# RP2350B.net
KiCad netlist of a schematic drawn in Altium Designer
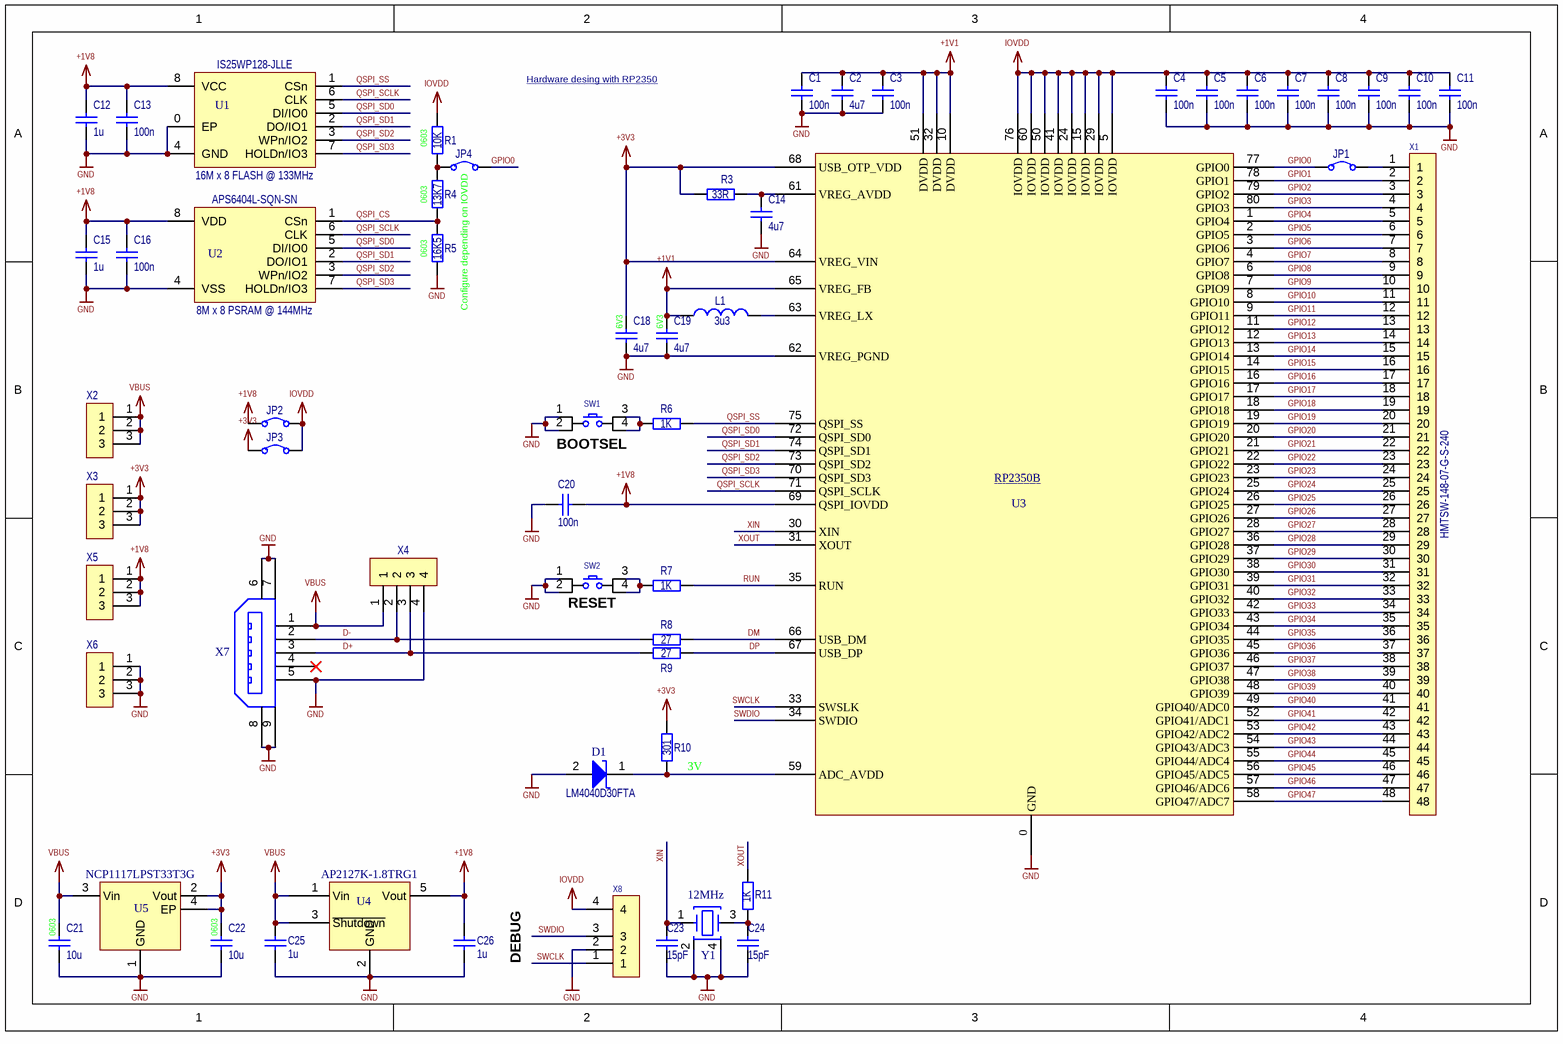
[diagram p0: RP2350B.SchDoc]

(export (version "E")
  (design (tool "Eeschema 10.0.6"))
  (components
    (comp (ref "C1")
      (value "100n")
      (footprint "CAPC0402")
      (description "Capacitor; Ceramic; 100n; 2; 10V; X7R; 5%; -55°C ~ 125°C")
      (fields (field (name "Comment") "C0402C104J8RACTU"))
      (libsource (lib "Capacitors") (part "100n_0402_10V_X7R_5%"))
    )
    (comp (ref "C2")
      (value "4u7")
      (footprint "CAPC0402")
      (description "Capacitor; Ceramic; 4.7u; 0402; 10V; X5R; 10%; -55°C ~ 85°C")
      (fields
        (field (name "MANUFACTURER") "Samsung Electro-Mechanics")
        (field (name "MANUFACTURER PART NUMBER") "CL05A475KP5NRNC")
      )
      (libsource (lib "Capacitors") (part "4u7_0402_10V_X5R_10%"))
    )
    (comp (ref "C3")
      (value "100n")
      (footprint "CAPC0402")
      (description "Capacitor; Ceramic; 100n; 0402; 10V; X7R; 5%; -55°C ~ 125°C")
      (fields (field (name "Comment") "C0402C104J8RACTU"))
      (libsource (lib "Capacitors") (part "100n_0402_10V_X7R_5%"))
    )
    (comp (ref "C4")
      (value "100n")
      (footprint "CAPC0402")
      (description "Capacitor; Ceramic; 100n; 0402; 10V; X7R; 5%; -55°C ~ 125°C")
      (fields (field (name "Comment") "C0402C104J8RACTU"))
      (libsource (lib "Capacitors") (part "100n_0402_10V_X7R_5%"))
    )
    (comp (ref "C5")
      (value "100n")
      (footprint "CAPC0402")
      (description "Capacitor; Ceramic; 100n; 0402; 10V; X7R; 5%; -55°C ~ 125°C")
      (fields (field (name "Comment") "C0402C104J8RACTU"))
      (libsource (lib "Capacitors") (part "100n_0402_10V_X7R_5%"))
    )
    (comp (ref "C6")
      (value "100n")
      (footprint "CAPC0402")
      (description "Capacitor; Ceramic; 100n; 0402; 10V; X7R; 5%; -55°C ~ 125°C")
      (fields (field (name "Comment") "C0402C104J8RACTU"))
      (libsource (lib "Capacitors") (part "100n_0402_10V_X7R_5%"))
    )
    (comp (ref "C7")
      (value "100n")
      (footprint "CAPC0402")
      (description "Capacitor; Ceramic; 100n; 0402; 10V; X7R; 5%; -55°C ~ 125°C")
      (fields (field (name "Comment") "C0402C104J8RACTU"))
      (libsource (lib "Capacitors") (part "100n_0402_10V_X7R_5%"))
    )
    (comp (ref "C8")
      (value "100n")
      (footprint "CAPC0402")
      (description "Capacitor; Ceramic; 100n; 0402; 10V; X7R; 5%; -55°C ~ 125°C")
      (fields (field (name "Comment") "C0402C104J8RACTU"))
      (libsource (lib "Capacitors") (part "100n_0402_10V_X7R_5%"))
    )
    (comp (ref "C9")
      (value "100n")
      (footprint "CAPC0402")
      (description "Capacitor; Ceramic; 100n; 0402; 10V; X7R; 5%; -55°C ~ 125°C")
      (fields (field (name "Comment") "C0402C104J8RACTU"))
      (libsource (lib "Capacitors") (part "100n_0402_10V_X7R_5%"))
    )
    (comp (ref "C10")
      (value "100n")
      (footprint "CAPC0402")
      (description "Capacitor; Ceramic; 100n; 0402; 10V; X7R; 5%; -55°C ~ 125°C")
      (fields (field (name "Comment") "C0402C104J8RACTU"))
      (libsource (lib "Capacitors") (part "100n_0402_10V_X7R_5%"))
    )
    (comp (ref "C11")
      (value "100n")
      (footprint "CAPC0402")
      (description "Capacitor; Ceramic; 100n; 0402; 10V; X7R; 5%; -55°C ~ 125°C")
      (fields (field (name "Comment") "C0402C104J8RACTU"))
      (libsource (lib "Capacitors") (part "100n_0402_10V_X7R_5%"))
    )
    (comp (ref "C12")
      (value "1u")
      (footprint "CAPC0402")
      (description "Capacitor; Ceramic; 1u; 0402; 10V; X5R; 10%; -55°C ~ 85°C")
      (fields
        (field (name "MANUFACTURER") "Samsung Electro-Mechanics")
        (field (name "MANUFACTURER PART NUMBER") "CL05A105KP5NNNC")
      )
      (libsource (lib "Capacitors") (part "1u_0402_10V_X5R_10%"))
    )
    (comp (ref "C13")
      (value "100n")
      (footprint "CAPC0402")
      (description "Capacitor; Ceramic; 100n; 0402; 10V; X7R; 5%; -55°C ~ 125°C")
      (fields (field (name "Comment") "C0402C104J8RACTU"))
      (libsource (lib "Capacitors") (part "100n_0402_10V_X7R_5%"))
    )
    (comp (ref "C14")
      (value "4u7")
      (footprint "CAPC0402")
      (description "Capacitor; Ceramic; 4.7u; 0402; 10V; X5R; 10%; -55°C ~ 85°C")
      (fields
        (field (name "MANUFACTURER") "Samsung Electro-Mechanics")
        (field (name "MANUFACTURER PART NUMBER") "CL05A475KP5NRNC")
      )
      (libsource (lib "Capacitors") (part "4u7_0402_10V_X5R_10%"))
    )
    (comp (ref "C15")
      (value "1u")
      (footprint "CAPC0402")
      (description "Capacitor; Ceramic; 1u; 0402; 10V; X5R; 10%; -55°C ~ 85°C")
      (fields
        (field (name "MANUFACTURER") "Samsung Electro-Mechanics")
        (field (name "MANUFACTURER PART NUMBER") "CL05A105KP5NNNC")
      )
      (libsource (lib "Capacitors") (part "1u_0402_10V_X5R_10%"))
    )
    (comp (ref "C16")
      (value "100n")
      (footprint "CAPC0402")
      (description "Capacitor; Ceramic; 100n; 0402; 10V; X7R; 5%; -55°C ~ 125°C")
      (fields (field (name "Comment") "C0402C104J8RACTU"))
      (libsource (lib "Capacitors") (part "100n_0402_10V_X7R_5%"))
    )
    (comp (ref "C18")
      (value "6V3")
      (footprint "CAPC0603")
      (description "Capacitor; Ceramic; 4.7u; 0603; 6.3V; X7S; 10%; -55°C ~ 125°C")
      (fields
        (field (name "MANUFACTURER") "Murata Electronics")
        (field (name "MANUFACTURER PART NUMBER") "GCJ188C70J475KE02D")
        (field (name "ALTIUM_VALUE") "4u7")
      )
      (libsource (lib "symbols") (part "4u7_0603_6V3_X7S_10%"))
    )
    (comp (ref "C19")
      (value "6V3")
      (footprint "CAPC0603")
      (description "Capacitor; Ceramic; 4.7u; 0603; 6.3V; X7S; 10%; -55°C ~ 125°C")
      (fields
        (field (name "MANUFACTURER") "Murata Electronics")
        (field (name "MANUFACTURER PART NUMBER") "GCJ188C70J475KE02D")
        (field (name "ALTIUM_VALUE") "4u7")
      )
      (libsource (lib "symbols") (part "4u7_0603_6V3_X7S_10%"))
    )
    (comp (ref "C20")
      (value "100n")
      (footprint "CAPC0402")
      (description "Capacitor; Ceramic; 100n; 0402; 10V; X7R; 5%; -55°C ~ 125°C")
      (fields (field (name "Comment") "C0402C104J8RACTU"))
      (libsource (lib "Capacitors") (part "100n_0402_10V_X7R_5%"))
    )
    (comp (ref "C21")
      (value "0603")
      (footprint "CAPC0603")
      (description "Capacitor; Ceramic; 10u; 0603; 16V; X5R; 10%; -55°C ~ 85°C")
      (fields (field (name "ALTIUM_VALUE") "10u"))
      (libsource (lib "Capacitors") (part "10u_0603_16V_X5R_10%"))
    )
    (comp (ref "C22")
      (value "0603")
      (footprint "CAPC0603")
      (description "Capacitor; Ceramic; 10u; 0603; 16V; X5R; 10%; -55°C ~ 85°C")
      (fields (field (name "ALTIUM_VALUE") "10u"))
      (libsource (lib "Capacitors") (part "10u_0603_16V_X5R_10%"))
    )
    (comp (ref "C23")
      (value "15pF")
      (footprint "CAPC0402")
      (description "Capacitor; Ceramic; 15p; 0402; 25V; C0G/NP0; +/-5%; -55°C ~ 125°C")
      (fields
        (field (name "MANUFACTURER") "YAGEO")
        (field (name "MANUFACTURER PART NUMBER") "CC0402JRNPO8BN150")
      )
      (libsource (lib "symbols") (part "15p_0402_25V_C0G/NP0_5%"))
    )
    (comp (ref "C24")
      (value "15pF")
      (footprint "CAPC0402")
      (description "Capacitor; Ceramic; 15p; 0402; 25V; C0G/NP0; +/-5%; -55°C ~ 125°C")
      (fields
        (field (name "MANUFACTURER") "YAGEO")
        (field (name "MANUFACTURER PART NUMBER") "CC0402JRNPO8BN150")
      )
      (libsource (lib "symbols") (part "15p_0402_25V_C0G/NP0_5%"))
    )
    (comp (ref "C25")
      (value "1u")
      (footprint "CAPC0402")
      (description "Capacitor; Ceramic; 1u; 0402; 10V; X5R; 10%; -55°C ~ 85°C")
      (fields
        (field (name "MANUFACTURER") "Samsung Electro-Mechanics")
        (field (name "MANUFACTURER PART NUMBER") "CL05A105KP5NNNC")
      )
      (libsource (lib "Capacitors") (part "1u_0402_10V_X5R_10%"))
    )
    (comp (ref "C26")
      (value "1u")
      (footprint "CAPC0402")
      (description "Capacitor; Ceramic; 1u; 0402; 10V; X5R; 10%; -55°C ~ 85°C")
      (fields
        (field (name "MANUFACTURER") "Samsung Electro-Mechanics")
        (field (name "MANUFACTURER PART NUMBER") "CL05A105KP5NNNC")
      )
      (libsource (lib "Capacitors") (part "1u_0402_10V_X5R_10%"))
    )
    (comp (ref "D1")
      (value "LM4040D30FTA")
      (footprint "SOT23-3")
      (description "Shunt Voltage Reference IC Fixed 3V ±1% 15 mA SOT-23-3")
      (fields (field (name "MANUFACTURER") "Diodes Incorporated") (field (name "ALTIUM_VALUE") "3V"))
      (libsource (lib "symbols") (part "LM4040D30FTA"))
    )
    (comp (ref "JP1")
      (value "5110 Keystone")
      (footprint "JumperSMD_0603")
      (description "Jumper; Chip; 0R; 0603; 500mW")
      (fields (field (name "MANUFACTURER") "Keystone") (field (name "MANUFACTURER PART NUMBER") "5110"))
      (libsource (lib "Jumpers") (part "JMP_0R_0603"))
    )
    (comp (ref "JP2")
      (value "5110 Keystone")
      (footprint "JumperSMD_0603")
      (description "Jumper; Chip; 0R; 0603; 500mW")
      (fields (field (name "MANUFACTURER") "Keystone") (field (name "MANUFACTURER PART NUMBER") "5110"))
      (libsource (lib "Jumpers") (part "JMP_0R_0603"))
    )
    (comp (ref "JP3")
      (value "5110 Keystone")
      (footprint "JumperSMD_0603")
      (description "Jumper; Chip; 0R; 0603; 500mW")
      (fields (field (name "MANUFACTURER") "Keystone") (field (name "MANUFACTURER PART NUMBER") "5110"))
      (libsource (lib "Jumpers") (part "JMP_0R_0603"))
    )
    (comp (ref "JP4")
      (value "5110 Keystone")
      (footprint "JumperSMD_0603")
      (description "Jumper; Chip; 0R; 0603; 500mW")
      (fields (field (name "MANUFACTURER") "Keystone") (field (name "MANUFACTURER PART NUMBER") "5110"))
      (libsource (lib "Jumpers") (part "JMP_0R_0603"))
    )
    (comp (ref "L1")
      (value "3u3")
      (footprint "IND_0806")
      (description "3.3 µH Shielded Inductor 1.4 A 225mOhm Max 0806")
      (fields
        (field (name "MANUFACTURER") "Bourns Inc.")
        (field (name "MANUFACTURER PART NUMBER") "SRP2010DPA-3R3M")
      )
      (libsource (lib "Inductances") (part "IND_3u3_2X1.6mm_1.4A_20%"))
    )
    (comp (ref "R1")
      (value "0603")
      (footprint "RESC0603")
      (description "Resistor; Chip; 10k; 0603; 75V; 1%; 100ppm; 100mW; -55°C ~ 155°C")
      (fields (field (name "ALTIUM_VALUE") "10K"))
      (libsource (lib "Resistors") (part "10K_0603_100mW_1%_100ppm"))
    )
    (comp (ref "R3")
      (value "33R")
      (footprint "RESC0402")
      (description "Resistor; Chip; 33R; 0402; 50V; 1%; 100ppm; 63mW; -55°C ~ 155°C")
      (fields
        (field (name "MANUFACTURER") "Yageo")
        (field (name "MANUFACTURER PART NUMBER") "RC0402FR-0733RL")
      )
      (libsource (lib "Resistors") (part "33R_0402_63mW_1%_100ppm"))
    )
    (comp (ref "R4")
      (value "0603")
      (footprint "RESC0603")
      (description "Resistor; Chip; 13K7; 0603; 0.1%; 25ppm; 100mW; -55°C ~ 155°C")
      (fields
        (field (name "MANUFACTURER") "YAGEO")
        (field (name "MANUFACTURER PART NUMBER") "RT0603BRD0713K7L")
        (field (name "ALTIUM_VALUE") "13K7")
      )
      (libsource (lib "symbols") (part "13K7_0603_100mW_0.1%_25ppm"))
    )
    (comp (ref "R5")
      (value "0603")
      (footprint "RESC0603")
      (description "Resistor; Chip; 16K5; 0603; 0.1%; 25ppm; 100mW; -55°C ~ 155°C")
      (fields
        (field (name "MANUFACTURER") "YAGEO")
        (field (name "MANUFACTURER PART NUMBER") "RT0603BRD0716K5L")
        (field (name "ALTIUM_VALUE") "16K5")
      )
      (libsource (lib "symbols") (part "16K5_0603_100mW_0.1%_25ppm"))
    )
    (comp (ref "R6")
      (value "1K")
      (footprint "RESC0402")
      (description "Resistor; Chip; 1k; 0402; 50V; 1%; 100ppm; 63mW; -55°C ~ 155°C")
      (fields
        (field (name "MANUFACTURER") "Yageo")
        (field (name "MANUFACTURER PART NUMBER") "RC0402FR-071KL")
      )
      (libsource (lib "Resistors") (part "1K_0402_63mW_1%_100ppm"))
    )
    (comp (ref "R7")
      (value "1K")
      (footprint "RESC0402")
      (description "Resistor; Chip; 1k; 0402; 50V; 1%; 100ppm; 63mW; -55°C ~ 155°C")
      (fields
        (field (name "MANUFACTURER") "Yageo")
        (field (name "MANUFACTURER PART NUMBER") "RC0402FR-071KL")
      )
      (libsource (lib "Resistors") (part "1K_0402_63mW_1%_100ppm"))
    )
    (comp (ref "R8")
      (value "27")
      (footprint "RESC0402")
      (description "Resistor; Chip; 27Ohm; 0402; 1%; 100ppm; 63mW; -55°C ~ 155°C")
      (fields
        (field (name "MANUFACTURER") "YAGEO")
        (field (name "MANUFACTURER PART NUMBER") "RC0402FR-0727RL")
      )
      (libsource (lib "symbols") (part "27R_0402_63mW_1%_100ppm"))
    )
    (comp (ref "R9")
      (value "27")
      (footprint "RESC0402")
      (description "Resistor; Chip; 27Ohm; 0402; 1%; 100ppm; 63mW; -55°C ~ 155°C")
      (fields
        (field (name "MANUFACTURER") "YAGEO")
        (field (name "MANUFACTURER PART NUMBER") "RC0402FR-0727RL")
      )
      (libsource (lib "symbols") (part "27R_0402_63mW_1%_100ppm"))
    )
    (comp (ref "R10")
      (value "301")
      (footprint "RESC0402")
      (description "Resistor; Chip; 301R; 0402; 1%; 100ppm; 63mW; -55°C ~ 155°C")
      (fields
        (field (name "MANUFACTURER") "YAGEO")
        (field (name "MANUFACTURER PART NUMBER") "RC0402FR-07301RL")
      )
      (libsource (lib "symbols") (part "301R_0402_63mW_1%_100ppm"))
    )
    (comp (ref "R11")
      (value "1K")
      (footprint "RESC0402")
      (description "Resistor; Chip; 1k; 0402; 50V; 1%; 100ppm; 63mW; -55°C ~ 155°C")
      (fields
        (field (name "MANUFACTURER") "Yageo")
        (field (name "MANUFACTURER PART NUMBER") "RC0402FR-071KL")
      )
      (libsource (lib "") (part "1K_0402_63mW_1%_100ppm_1"))
    )
    (comp (ref "SW1")
      (value "434133025816")
      (footprint "434133025816")
      (description "SWITCH TACTILE SPST-NO 0.05A 16V")
      (fields (field (name "MANUFACTURER") "Würth Elektronik"))
      (libsource (lib "symbols") (part "434133025816"))
    )
    (comp (ref "SW2")
      (value "434133025816")
      (footprint "434133025816")
      (description "SWITCH TACTILE SPST-NO 0.05A 16V")
      (fields (field (name "MANUFACTURER") "Würth Elektronik"))
      (libsource (lib "symbols") (part "434133025816"))
    )
    (comp (ref "U1")
      (value "16M x 8 FLASH @ 133MHz")
      (footprint "WSON8-6x8")
      (description "IC FLASH 128MBIT SPI/QUAD 8WSON")
      (fields
        (field (name "MANUFACTURER") "ISSI, Integrated Silicon Solution Inc")
        (field (name "MANUFACTURER PART NUMBER") "IS25WP128-JLLE")
        (field (name "Comment") "IS25WP128-JLLE")
      )
      (libsource (lib "symbols") (part "IS25WP128-JLLE"))
    )
    (comp (ref "U2")
      (value "8M x 8 PSRAM @ 144MHz")
      (footprint "SOP-8L (150)")
      (description "IC PSRAM 64MBIT QSPI SOP-8L")
      (fields
        (field (name "MANUFACTURER") "AP Memory")
        (field (name "MANUFACTURER PART NUMBER") "APS6404L-SQN-SN")
        (field (name "Comment") "APS6404L-SQN-SN")
      )
      (libsource (lib "symbols") (part "APS6404L-SQN-SN"))
    )
    (comp (ref "U3")
      (value "RP2350B")
      (footprint "QFN-80")
      (description "IC MCU 32BIT EXT MEM 80QFN")
      (libsource (lib "symbols") (part "RP2350B"))
    )
    (comp (ref "U4")
      (value "AP2127K-1.8TRG1")
      (footprint "SOT23-5")
      (description "IC REG LINEAR 1.8V 300MA SOT23-5")
      (fields
        (field (name "MANUFACTURER") "Diodes Incorporated")
        (field (name "MANUFACTURER PART NUMBER") "AP2127K-1.8TRG1")
      )
      (libsource (lib "symbols") (part "AP2127K-1.8TRG1"))
    )
    (comp (ref "U5")
      (value "NCP1117LPST33T3G")
      (footprint "SOT-232-4")
      (description "IC REG LINEAR 3.3V 1A SOT223")
      (fields (field (name "MANUFACTURER") "onsemi"))
      (libsource (lib "symbols") (part "NCP1117LPST33T3G"))
    )
    (comp (ref "X1")
      (value "HMTSW-148-07-G-S-240")
      (footprint "HDR_TH_1X48_M_00")
      (description "Header; 1x48 pins; Male; Straight; Pitch 2.54mm; Samtec HMTSW Series")
      (libsource (lib "symbols") (part "HDR_TH_1X48_M_00"))
    )
    (comp (ref "X2")
      (value "825433-3")
      (footprint "HDR_TH_1X3_M_00")
      (description "Header; 1x3 pins; Male; Straight; Pitch 2.54mm")
      (fields
        (field (name "MANUFACTURER") "TE Connectivity")
        (field (name "MANUFACTURER PART NUMBER") "825433-2")
      )
      (libsource (lib "Connections") (part "HDR_TH_1X3_M_00"))
    )
    (comp (ref "X3")
      (value "825433-3")
      (footprint "HDR_TH_1X3_M_00")
      (description "Header; 1x3 pins; Male; Straight; Pitch 2.54mm")
      (fields
        (field (name "MANUFACTURER") "TE Connectivity")
        (field (name "MANUFACTURER PART NUMBER") "825433-2")
      )
      (libsource (lib "Connections") (part "HDR_TH_1X3_M_00"))
    )
    (comp (ref "X4")
      (value "HMTSW-104-07-G-S-240")
      (footprint "HDR_TH_1X4_M_00")
      (description "Header; 1x4 pins; Male; Straight; Pitch 2.54mm; Samtec HMTSW Series")
      (libsource (lib "symbols") (part "HDR_TH_1X4_M_00"))
    )
    (comp (ref "X5")
      (value "825433-3")
      (footprint "HDR_TH_1X3_M_00")
      (description "Header; 1x3 pins; Male; Straight; Pitch 2.54mm")
      (fields
        (field (name "MANUFACTURER") "TE Connectivity")
        (field (name "MANUFACTURER PART NUMBER") "825433-2")
      )
      (libsource (lib "Connections") (part "HDR_TH_1X3_M_00"))
    )
    (comp (ref "X6")
      (value "825433-3")
      (footprint "HDR_TH_1X3_M_00")
      (description "Header; 1x3 pins; Male; Straight; Pitch 2.54mm")
      (fields
        (field (name "MANUFACTURER") "TE Connectivity")
        (field (name "MANUFACTURER PART NUMBER") "825433-2")
      )
      (libsource (lib "Connections") (part "HDR_TH_1X3_M_00"))
    )
    (comp (ref "X7")
      (value "1734327-1")
      (footprint "1734327-1")
      (description "USB - mini A USB 2.0 Receptacle Connector 5 Position Surface Mount, Right Angle")
      (fields (field (name "MANUFACTURER") "TE Connectivity AMP Connectors"))
      (libsource (lib "symbols") (part "1734327-1"))
    )
    (comp (ref "X8")
      (value "HMTSW-106-07-G-S-240")
      (footprint "HDR_TH_1X3+0+1_M_00")
      (description "Header; 1x5 pins (with key); Male; Straight; Pitch 2.54mm; Samtec HMTSW Series")
      (fields
        (field (name "MANUFACTURER") "Samtec Inc.")
        (field (name "MANUFACTURER PART NUMBER") "HMTSW-105-07-G-S-240")
      )
      (libsource (lib "symbols") (part "HDR_TH_1X3+1_M_00"))
    )
    (comp (ref "Y1")
      (value "12MHz")
      (footprint "ABM8")
      (description "Christal; SMD; 12 MHz ±30ppm; 10pF/50Ohm")
      (fields
        (field (name "MANUFACTURER") "Abracon LLC")
        (field (name "MANUFACTURER PART NUMBER") "ABM8-272-T3")
      )
      (libsource (lib "symbols") (part "ABM8-272-T3"))
    )
  )
  (nets
    (net (code "1") (name "+1V1") (class "Default")
      (node (ref "C1") (pin "2") (pinfunction "2_2") (pintype "passive"))
      (node (ref "C19") (pin "2") (pinfunction "2_2") (pintype "passive"))
      (node (ref "C2") (pin "2") (pinfunction "2_2") (pintype "passive"))
      (node (ref "C3") (pin "2") (pinfunction "2_2") (pintype "passive"))
      (node (ref "L1") (pin "1") (pinfunction "1_1") (pintype "passive"))
      (node (ref "U3") (pin "10") (pinfunction "DVDD_10") (pintype "passive"))
      (node (ref "U3") (pin "32") (pinfunction "DVDD_32") (pintype "passive"))
      (node (ref "U3") (pin "51") (pinfunction "DVDD_51") (pintype "passive"))
      (node (ref "U3") (pin "65") (pinfunction "VREG_FB_65") (pintype "passive"))
    )
    (net (code "2") (name "+1V8") (class "Default")
      (node (ref "C12") (pin "1") (pinfunction "1_1") (pintype "passive"))
      (node (ref "C13") (pin "2") (pinfunction "2_2") (pintype "passive"))
      (node (ref "C15") (pin "1") (pinfunction "1_1") (pintype "passive"))
      (node (ref "C16") (pin "2") (pinfunction "2_2") (pintype "passive"))
      (node (ref "C20") (pin "2") (pinfunction "2_2") (pintype "passive"))
      (node (ref "C26") (pin "1") (pinfunction "1_1") (pintype "passive"))
      (node (ref "JP2") (pin "1") (pinfunction "1_1") (pintype "passive"))
      (node (ref "U1") (pin "8") (pinfunction "VCC_8") (pintype "passive"))
      (node (ref "U2") (pin "8") (pinfunction "VDD_8") (pintype "passive"))
      (node (ref "U3") (pin "69") (pinfunction "QSPI_IOVDD_69") (pintype "passive"))
      (node (ref "U4") (pin "5") (pinfunction "Vout_5") (pintype "passive"))
      (node (ref "X5") (pin "1") (pinfunction "1_1") (pintype "passive"))
      (node (ref "X5") (pin "2") (pinfunction "2_2") (pintype "passive"))
      (node (ref "X5") (pin "3") (pinfunction "3_3") (pintype "passive"))
    )
    (net (code "3") (name "+3V3") (class "Default")
      (node (ref "C18") (pin "2") (pinfunction "2_2") (pintype "passive"))
      (node (ref "C22") (pin "2") (pinfunction "2_2") (pintype "passive"))
      (node (ref "JP3") (pin "1") (pinfunction "1_1") (pintype "passive"))
      (node (ref "R10") (pin "2") (pinfunction "2_2") (pintype "passive"))
      (node (ref "R3") (pin "1") (pinfunction "1_1") (pintype "passive"))
      (node (ref "U3") (pin "64") (pinfunction "VREG_VIN_64") (pintype "passive"))
      (node (ref "U3") (pin "68") (pinfunction "USB_OTP_VDD_68") (pintype "passive"))
      (node (ref "U5") (pin "2") (pinfunction "Vout_2") (pintype "passive"))
      (node (ref "U5") (pin "4") (pinfunction "EP_4") (pintype "passive"))
      (node (ref "X3") (pin "1") (pinfunction "1_1") (pintype "passive"))
      (node (ref "X3") (pin "2") (pinfunction "2_2") (pintype "passive"))
      (node (ref "X3") (pin "3") (pinfunction "3_3") (pintype "passive"))
    )
    (net (code "4") (name "/D+") (class "Default")
      (node (ref "R9") (pin "1") (pinfunction "1_1") (pintype "passive"))
      (node (ref "X4") (pin "3") (pinfunction "3_3") (pintype "passive"))
      (node (ref "X7") (pin "3") (pinfunction "3_3") (pintype "passive"))
    )
    (net (code "5") (name "/D-") (class "Default")
      (node (ref "R8") (pin "1") (pinfunction "1_1") (pintype "passive"))
      (node (ref "X4") (pin "2") (pinfunction "2_2") (pintype "passive"))
      (node (ref "X7") (pin "2") (pinfunction "2_2") (pintype "passive"))
    )
    (net (code "6") (name "/DM") (class "Default")
      (node (ref "R8") (pin "2") (pinfunction "2_2") (pintype "passive"))
      (node (ref "U3") (pin "66") (pinfunction "USB_DM_66") (pintype "passive"))
    )
    (net (code "7") (name "/DP") (class "Default")
      (node (ref "R9") (pin "2") (pinfunction "2_2") (pintype "passive"))
      (node (ref "U3") (pin "67") (pinfunction "USB_DP_67") (pintype "passive"))
    )
    (net (code "8") (name "/GPIO0") (class "Default")
      (node (ref "JP1") (pin "1") (pinfunction "1_1") (pintype "passive"))
      (node (ref "JP4") (pin "2") (pinfunction "2_2") (pintype "passive"))
      (node (ref "U3") (pin "77") (pinfunction "GPIO0_77") (pintype "passive"))
    )
    (net (code "9") (name "/GPIO1") (class "Default")
      (node (ref "U3") (pin "78") (pinfunction "GPIO1_78") (pintype "passive"))
      (node (ref "X1") (pin "2") (pinfunction "2_2") (pintype "passive"))
    )
    (net (code "10") (name "/GPIO2") (class "Default")
      (node (ref "U3") (pin "79") (pinfunction "GPIO2_79") (pintype "passive"))
      (node (ref "X1") (pin "3") (pinfunction "3_3") (pintype "passive"))
    )
    (net (code "11") (name "/GPIO3") (class "Default")
      (node (ref "U3") (pin "80") (pinfunction "GPIO3_80") (pintype "passive"))
      (node (ref "X1") (pin "4") (pinfunction "4_4") (pintype "passive"))
    )
    (net (code "12") (name "/GPIO4") (class "Default")
      (node (ref "U3") (pin "1") (pinfunction "GPIO4_1") (pintype "passive"))
      (node (ref "X1") (pin "5") (pinfunction "5_5") (pintype "passive"))
    )
    (net (code "13") (name "/GPIO5") (class "Default")
      (node (ref "U3") (pin "2") (pinfunction "GPIO5_2") (pintype "passive"))
      (node (ref "X1") (pin "6") (pinfunction "6_6") (pintype "passive"))
    )
    (net (code "14") (name "/GPIO6") (class "Default")
      (node (ref "U3") (pin "3") (pinfunction "GPIO6_3") (pintype "passive"))
      (node (ref "X1") (pin "7") (pinfunction "7_7") (pintype "passive"))
    )
    (net (code "15") (name "/GPIO7") (class "Default")
      (node (ref "U3") (pin "4") (pinfunction "GPIO7_4") (pintype "passive"))
      (node (ref "X1") (pin "8") (pinfunction "8_8") (pintype "passive"))
    )
    (net (code "16") (name "/GPIO8") (class "Default")
      (node (ref "U3") (pin "6") (pinfunction "GPIO8_6") (pintype "passive"))
      (node (ref "X1") (pin "9") (pinfunction "9_9") (pintype "passive"))
    )
    (net (code "17") (name "/GPIO9") (class "Default")
      (node (ref "U3") (pin "7") (pinfunction "GPIO9_7") (pintype "passive"))
      (node (ref "X1") (pin "10") (pinfunction "10_10") (pintype "passive"))
    )
    (net (code "18") (name "/GPIO10") (class "Default")
      (node (ref "U3") (pin "8") (pinfunction "GPIO10_8") (pintype "passive"))
      (node (ref "X1") (pin "11") (pinfunction "11_11") (pintype "passive"))
    )
    (net (code "19") (name "/GPIO11") (class "Default")
      (node (ref "U3") (pin "9") (pinfunction "GPIO11_9") (pintype "passive"))
      (node (ref "X1") (pin "12") (pinfunction "12_12") (pintype "passive"))
    )
    (net (code "20") (name "/GPIO12") (class "Default")
      (node (ref "U3") (pin "11") (pinfunction "GPIO12_11") (pintype "passive"))
      (node (ref "X1") (pin "13") (pinfunction "13_13") (pintype "passive"))
    )
    (net (code "21") (name "/GPIO13") (class "Default")
      (node (ref "U3") (pin "12") (pinfunction "GPIO13_12") (pintype "passive"))
      (node (ref "X1") (pin "14") (pinfunction "14_14") (pintype "passive"))
    )
    (net (code "22") (name "/GPIO14") (class "Default")
      (node (ref "U3") (pin "13") (pinfunction "GPIO14_13") (pintype "passive"))
      (node (ref "X1") (pin "15") (pinfunction "15_15") (pintype "passive"))
    )
    (net (code "23") (name "/GPIO15") (class "Default")
      (node (ref "U3") (pin "14") (pinfunction "GPIO15_14") (pintype "passive"))
      (node (ref "X1") (pin "16") (pinfunction "16_16") (pintype "passive"))
    )
    (net (code "24") (name "/GPIO16") (class "Default")
      (node (ref "U3") (pin "16") (pinfunction "GPIO16_16") (pintype "passive"))
      (node (ref "X1") (pin "17") (pinfunction "17_17") (pintype "passive"))
    )
    (net (code "25") (name "/GPIO17") (class "Default")
      (node (ref "U3") (pin "17") (pinfunction "GPIO17_17") (pintype "passive"))
      (node (ref "X1") (pin "18") (pinfunction "18_18") (pintype "passive"))
    )
    (net (code "26") (name "/GPIO18") (class "Default")
      (node (ref "U3") (pin "18") (pinfunction "GPIO18_18") (pintype "passive"))
      (node (ref "X1") (pin "19") (pinfunction "19_19") (pintype "passive"))
    )
    (net (code "27") (name "/GPIO19") (class "Default")
      (node (ref "U3") (pin "19") (pinfunction "GPIO19_19") (pintype "passive"))
      (node (ref "X1") (pin "20") (pinfunction "20_20") (pintype "passive"))
    )
    (net (code "28") (name "/GPIO20") (class "Default")
      (node (ref "U3") (pin "20") (pinfunction "GPIO20_20") (pintype "passive"))
      (node (ref "X1") (pin "21") (pinfunction "21_21") (pintype "passive"))
    )
    (net (code "29") (name "/GPIO21") (class "Default")
      (node (ref "U3") (pin "21") (pinfunction "GPIO21_21") (pintype "passive"))
      (node (ref "X1") (pin "22") (pinfunction "22_22") (pintype "passive"))
    )
    (net (code "30") (name "/GPIO22") (class "Default")
      (node (ref "U3") (pin "22") (pinfunction "GPIO22_22") (pintype "passive"))
      (node (ref "X1") (pin "23") (pinfunction "23_23") (pintype "passive"))
    )
    (net (code "31") (name "/GPIO23") (class "Default")
      (node (ref "U3") (pin "23") (pinfunction "GPIO23_23") (pintype "passive"))
      (node (ref "X1") (pin "24") (pinfunction "24_24") (pintype "passive"))
    )
    (net (code "32") (name "/GPIO24") (class "Default")
      (node (ref "U3") (pin "25") (pinfunction "GPIO24_25") (pintype "passive"))
      (node (ref "X1") (pin "25") (pinfunction "25_25") (pintype "passive"))
    )
    (net (code "33") (name "/GPIO25") (class "Default")
      (node (ref "U3") (pin "26") (pinfunction "GPIO25_26") (pintype "passive"))
      (node (ref "X1") (pin "26") (pinfunction "26_26") (pintype "passive"))
    )
    (net (code "34") (name "/GPIO26") (class "Default")
      (node (ref "U3") (pin "27") (pinfunction "GPIO26_27") (pintype "passive"))
      (node (ref "X1") (pin "27") (pinfunction "27_27") (pintype "passive"))
    )
    (net (code "35") (name "/GPIO27") (class "Default")
      (node (ref "U3") (pin "28") (pinfunction "GPIO27_28") (pintype "passive"))
      (node (ref "X1") (pin "28") (pinfunction "28_28") (pintype "passive"))
    )
    (net (code "36") (name "/GPIO28") (class "Default")
      (node (ref "U3") (pin "36") (pinfunction "GPIO28_36") (pintype "passive"))
      (node (ref "X1") (pin "29") (pinfunction "29_29") (pintype "passive"))
    )
    (net (code "37") (name "/GPIO29") (class "Default")
      (node (ref "U3") (pin "37") (pinfunction "GPIO29_37") (pintype "passive"))
      (node (ref "X1") (pin "30") (pinfunction "30_30") (pintype "passive"))
    )
    (net (code "38") (name "/GPIO30") (class "Default")
      (node (ref "U3") (pin "38") (pinfunction "GPIO30_38") (pintype "passive"))
      (node (ref "X1") (pin "31") (pinfunction "31_31") (pintype "passive"))
    )
    (net (code "39") (name "/GPIO31") (class "Default")
      (node (ref "U3") (pin "39") (pinfunction "GPIO31_39") (pintype "passive"))
      (node (ref "X1") (pin "32") (pinfunction "32_32") (pintype "passive"))
    )
    (net (code "40") (name "/GPIO32") (class "Default")
      (node (ref "U3") (pin "40") (pinfunction "GPIO32_40") (pintype "passive"))
      (node (ref "X1") (pin "33") (pinfunction "33_33") (pintype "passive"))
    )
    (net (code "41") (name "/GPIO33") (class "Default")
      (node (ref "U3") (pin "42") (pinfunction "GPIO33_42") (pintype "passive"))
      (node (ref "X1") (pin "34") (pinfunction "34_34") (pintype "passive"))
    )
    (net (code "42") (name "/GPIO34") (class "Default")
      (node (ref "U3") (pin "43") (pinfunction "GPIO34_43") (pintype "passive"))
      (node (ref "X1") (pin "35") (pinfunction "35_35") (pintype "passive"))
    )
    (net (code "43") (name "/GPIO35") (class "Default")
      (node (ref "U3") (pin "44") (pinfunction "GPIO35_44") (pintype "passive"))
      (node (ref "X1") (pin "36") (pinfunction "36_36") (pintype "passive"))
    )
    (net (code "44") (name "/GPIO36") (class "Default")
      (node (ref "U3") (pin "45") (pinfunction "GPIO36_45") (pintype "passive"))
      (node (ref "X1") (pin "37") (pinfunction "37_37") (pintype "passive"))
    )
    (net (code "45") (name "/GPIO37") (class "Default")
      (node (ref "U3") (pin "46") (pinfunction "GPIO37_46") (pintype "passive"))
      (node (ref "X1") (pin "38") (pinfunction "38_38") (pintype "passive"))
    )
    (net (code "46") (name "/GPIO38") (class "Default")
      (node (ref "U3") (pin "47") (pinfunction "GPIO38_47") (pintype "passive"))
      (node (ref "X1") (pin "39") (pinfunction "39_39") (pintype "passive"))
    )
    (net (code "47") (name "/GPIO39") (class "Default")
      (node (ref "U3") (pin "48") (pinfunction "GPIO39_48") (pintype "passive"))
      (node (ref "X1") (pin "40") (pinfunction "40_40") (pintype "passive"))
    )
    (net (code "48") (name "/GPIO40") (class "Default")
      (node (ref "U3") (pin "49") (pinfunction "GPIO40/ADC0_49") (pintype "passive"))
      (node (ref "X1") (pin "41") (pinfunction "41_41") (pintype "passive"))
    )
    (net (code "49") (name "/GPIO41") (class "Default")
      (node (ref "U3") (pin "52") (pinfunction "GPIO41/ADC1_52") (pintype "passive"))
      (node (ref "X1") (pin "42") (pinfunction "42_42") (pintype "passive"))
    )
    (net (code "50") (name "/GPIO42") (class "Default")
      (node (ref "U3") (pin "53") (pinfunction "GPIO42/ADC2_53") (pintype "passive"))
      (node (ref "X1") (pin "43") (pinfunction "43_43") (pintype "passive"))
    )
    (net (code "51") (name "/GPIO43") (class "Default")
      (node (ref "U3") (pin "54") (pinfunction "GPIO43/ADC3_54") (pintype "passive"))
      (node (ref "X1") (pin "44") (pinfunction "44_44") (pintype "passive"))
    )
    (net (code "52") (name "/GPIO44") (class "Default")
      (node (ref "U3") (pin "55") (pinfunction "GPIO44/ADC4_55") (pintype "passive"))
      (node (ref "X1") (pin "45") (pinfunction "45_45") (pintype "passive"))
    )
    (net (code "53") (name "/GPIO45") (class "Default")
      (node (ref "U3") (pin "56") (pinfunction "GPIO45/ADC5_56") (pintype "passive"))
      (node (ref "X1") (pin "46") (pinfunction "46_46") (pintype "passive"))
    )
    (net (code "54") (name "/GPIO46") (class "Default")
      (node (ref "U3") (pin "57") (pinfunction "GPIO46/ADC6_57") (pintype "passive"))
      (node (ref "X1") (pin "47") (pinfunction "47_47") (pintype "passive"))
    )
    (net (code "55") (name "/GPIO47") (class "Default")
      (node (ref "U3") (pin "58") (pinfunction "GPIO47/ADC7_58") (pintype "passive"))
      (node (ref "X1") (pin "48") (pinfunction "48_48") (pintype "passive"))
    )
    (net (code "56") (name "/QSPI_CS") (class "Default")
      (node (ref "R4") (pin "1") (pinfunction "1_1") (pintype "passive"))
      (node (ref "R5") (pin "2") (pinfunction "2_2") (pintype "passive"))
      (node (ref "U2") (pin "1") (pinfunction "CSn_1") (pintype "passive"))
    )
    (net (code "57") (name "/QSPI_SCLK") (class "Default")
      (node (ref "U1") (pin "6") (pinfunction "CLK_6") (pintype "passive"))
      (node (ref "U2") (pin "6") (pinfunction "CLK_6") (pintype "passive"))
      (node (ref "U3") (pin "71") (pinfunction "QSPI_SCLK_71") (pintype "passive"))
    )
    (net (code "58") (name "/QSPI_SD0") (class "Default")
      (node (ref "U1") (pin "5") (pinfunction "DI/IO0_5") (pintype "passive"))
      (node (ref "U2") (pin "5") (pinfunction "DI/IO0_5") (pintype "passive"))
      (node (ref "U3") (pin "72") (pinfunction "QSPI_SD0_72") (pintype "passive"))
    )
    (net (code "59") (name "/QSPI_SD1") (class "Default")
      (node (ref "U1") (pin "2") (pinfunction "DO/IO1_2") (pintype "passive"))
      (node (ref "U2") (pin "2") (pinfunction "DO/IO1_2") (pintype "passive"))
      (node (ref "U3") (pin "74") (pinfunction "QSPI_SD1_74") (pintype "passive"))
    )
    (net (code "60") (name "/QSPI_SD2") (class "Default")
      (node (ref "U1") (pin "3") (pinfunction "WPn/IO2_3") (pintype "passive"))
      (node (ref "U2") (pin "3") (pinfunction "WPn/IO2_3") (pintype "passive"))
      (node (ref "U3") (pin "73") (pinfunction "QSPI_SD2_73") (pintype "passive"))
    )
    (net (code "61") (name "/QSPI_SD3") (class "Default")
      (node (ref "U1") (pin "7") (pinfunction "HOLDn/IO3_7") (pintype "passive"))
      (node (ref "U2") (pin "7") (pinfunction "HOLDn/IO3_7") (pintype "passive"))
      (node (ref "U3") (pin "70") (pinfunction "QSPI_SD3_70") (pintype "passive"))
    )
    (net (code "62") (name "/QSPI_SS") (class "Default")
      (node (ref "R6") (pin "2") (pinfunction "2_2") (pintype "passive"))
      (node (ref "U1") (pin "1") (pinfunction "CSn_1") (pintype "passive"))
      (node (ref "U3") (pin "75") (pinfunction "QSPI_SS_75") (pintype "passive"))
    )
    (net (code "63") (name "/RUN") (class "Default")
      (node (ref "R7") (pin "2") (pinfunction "2_2") (pintype "passive"))
      (node (ref "U3") (pin "35") (pinfunction "RUN_35") (pintype "passive"))
    )
    (net (code "64") (name "/SWCLK") (class "Default")
      (node (ref "U3") (pin "33") (pinfunction "SWSLK_33") (pintype "passive"))
      (node (ref "X8") (pin "1") (pinfunction "1_1") (pintype "passive"))
    )
    (net (code "65") (name "/SWDIO") (class "Default")
      (node (ref "U3") (pin "34") (pinfunction "SWDIO_34") (pintype "passive"))
      (node (ref "X8") (pin "3") (pinfunction "3_3") (pintype "passive"))
    )
    (net (code "66") (name "/XIN") (class "Default")
      (node (ref "C23") (pin "2") (pinfunction "2_2") (pintype "passive"))
      (node (ref "U3") (pin "30") (pinfunction "XIN_30") (pintype "passive"))
      (node (ref "Y1") (pin "1") (pinfunction "IN_1") (pintype "passive"))
    )
    (net (code "67") (name "/XOUT") (class "Default")
      (node (ref "R11") (pin "2") (pinfunction "2_2") (pintype "passive"))
      (node (ref "U3") (pin "31") (pinfunction "XOUT_31") (pintype "passive"))
    )
    (net (code "68") (name "GND") (class "Default")
      (node (ref "C1") (pin "1") (pinfunction "1_1") (pintype "passive"))
      (node (ref "C10") (pin "1") (pinfunction "1_1") (pintype "passive"))
      (node (ref "C11") (pin "1") (pinfunction "1_1") (pintype "passive"))
      (node (ref "C12") (pin "2") (pinfunction "2_2") (pintype "passive"))
      (node (ref "C13") (pin "1") (pinfunction "1_1") (pintype "passive"))
      (node (ref "C14") (pin "1") (pinfunction "1_1") (pintype "passive"))
      (node (ref "C15") (pin "2") (pinfunction "2_2") (pintype "passive"))
      (node (ref "C16") (pin "1") (pinfunction "1_1") (pintype "passive"))
      (node (ref "C18") (pin "1") (pinfunction "1_1") (pintype "passive"))
      (node (ref "C19") (pin "1") (pinfunction "1_1") (pintype "passive"))
      (node (ref "C2") (pin "1") (pinfunction "1_1") (pintype "passive"))
      (node (ref "C20") (pin "1") (pinfunction "1_1") (pintype "passive"))
      (node (ref "C21") (pin "1") (pinfunction "1_1") (pintype "passive"))
      (node (ref "C22") (pin "1") (pinfunction "1_1") (pintype "passive"))
      (node (ref "C23") (pin "1") (pinfunction "1_1") (pintype "passive"))
      (node (ref "C24") (pin "1") (pinfunction "1_1") (pintype "passive"))
      (node (ref "C25") (pin "2") (pinfunction "2_2") (pintype "passive"))
      (node (ref "C26") (pin "2") (pinfunction "2_2") (pintype "passive"))
      (node (ref "C3") (pin "1") (pinfunction "1_1") (pintype "passive"))
      (node (ref "C4") (pin "1") (pinfunction "1_1") (pintype "passive"))
      (node (ref "C5") (pin "1") (pinfunction "1_1") (pintype "passive"))
      (node (ref "C6") (pin "1") (pinfunction "1_1") (pintype "passive"))
      (node (ref "C7") (pin "1") (pinfunction "1_1") (pintype "passive"))
      (node (ref "C8") (pin "1") (pinfunction "1_1") (pintype "passive"))
      (node (ref "C9") (pin "1") (pinfunction "1_1") (pintype "passive"))
      (node (ref "D1") (pin "2") (pinfunction "Anode_2") (pintype "passive"))
      (node (ref "R5") (pin "1") (pinfunction "1_1") (pintype "passive"))
      (node (ref "SW1") (pin "1") (pinfunction "1_1") (pintype "passive"))
      (node (ref "SW1") (pin "2") (pinfunction "2_2") (pintype "passive"))
      (node (ref "SW2") (pin "1") (pinfunction "1_1") (pintype "passive"))
      (node (ref "SW2") (pin "2") (pinfunction "2_2") (pintype "passive"))
      (node (ref "U1") (pin "0") (pinfunction "EP_0") (pintype "passive"))
      (node (ref "U1") (pin "4") (pinfunction "GND_4") (pintype "passive"))
      (node (ref "U2") (pin "4") (pinfunction "VSS_4") (pintype "passive"))
      (node (ref "U3") (pin "0") (pinfunction "GND_0") (pintype "passive"))
      (node (ref "U3") (pin "62") (pinfunction "VREG_PGND_62") (pintype "passive"))
      (node (ref "U4") (pin "2") (pinfunction "GND_2") (pintype "passive"))
      (node (ref "U5") (pin "1") (pinfunction "GND_1") (pintype "passive"))
      (node (ref "X4") (pin "4") (pinfunction "4_4") (pintype "passive"))
      (node (ref "X6") (pin "1") (pinfunction "1_1") (pintype "passive"))
      (node (ref "X6") (pin "2") (pinfunction "2_2") (pintype "passive"))
      (node (ref "X6") (pin "3") (pinfunction "3_3") (pintype "passive"))
      (node (ref "X7") (pin "5") (pinfunction "5_5") (pintype "passive"))
      (node (ref "X7") (pin "6") (pinfunction "6_6") (pintype "passive"))
      (node (ref "X7") (pin "7") (pinfunction "7_7") (pintype "passive"))
      (node (ref "X7") (pin "8") (pinfunction "8_8") (pintype "passive"))
      (node (ref "X7") (pin "9") (pinfunction "9_9") (pintype "passive"))
      (node (ref "X8") (pin "2") (pinfunction "2_2") (pintype "passive"))
      (node (ref "Y1") (pin "2") (pinfunction "GND_2") (pintype "passive"))
      (node (ref "Y1") (pin "4") (pinfunction "GND_4") (pintype "passive"))
    )
    (net (code "69") (name "IOVDD") (class "Default")
      (node (ref "C10") (pin "2") (pinfunction "2_2") (pintype "passive"))
      (node (ref "C11") (pin "2") (pinfunction "2_2") (pintype "passive"))
      (node (ref "C4") (pin "2") (pinfunction "2_2") (pintype "passive"))
      (node (ref "C5") (pin "2") (pinfunction "2_2") (pintype "passive"))
      (node (ref "C6") (pin "2") (pinfunction "2_2") (pintype "passive"))
      (node (ref "C7") (pin "2") (pinfunction "2_2") (pintype "passive"))
      (node (ref "C8") (pin "2") (pinfunction "2_2") (pintype "passive"))
      (node (ref "C9") (pin "2") (pinfunction "2_2") (pintype "passive"))
      (node (ref "JP2") (pin "2") (pinfunction "2_2") (pintype "passive"))
      (node (ref "JP3") (pin "2") (pinfunction "2_2") (pintype "passive"))
      (node (ref "R1") (pin "2") (pinfunction "2_2") (pintype "passive"))
      (node (ref "U3") (pin "15") (pinfunction "IOVDD_15") (pintype "passive"))
      (node (ref "U3") (pin "24") (pinfunction "IOVDD_24") (pintype "passive"))
      (node (ref "U3") (pin "29") (pinfunction "IOVDD_29") (pintype "passive"))
      (node (ref "U3") (pin "41") (pinfunction "IOVDD_41") (pintype "passive"))
      (node (ref "U3") (pin "5") (pinfunction "IOVDD_5") (pintype "passive"))
      (node (ref "U3") (pin "50") (pinfunction "IOVDD_50") (pintype "passive"))
      (node (ref "U3") (pin "60") (pinfunction "IOVDD_60") (pintype "passive"))
      (node (ref "U3") (pin "76") (pinfunction "IOVDD_76") (pintype "passive"))
      (node (ref "X8") (pin "4") (pinfunction "4_4") (pintype "passive"))
    )
    (net (code "70") (name "Net-(D1-Cathode)") (class "Default")
      (node (ref "D1") (pin "1") (pinfunction "Cathode_1") (pintype "passive"))
      (node (ref "R10") (pin "1") (pinfunction "1_1") (pintype "passive"))
      (node (ref "U3") (pin "59") (pinfunction "ADC_AVDD_59") (pintype "passive"))
    )
    (net (code "71") (name "Net-(JP1-Pad2)") (class "Default")
      (node (ref "JP1") (pin "2") (pinfunction "2_2") (pintype "passive"))
      (node (ref "X1") (pin "1") (pinfunction "1_1") (pintype "passive"))
    )
    (net (code "72") (name "Net-(JP4-Pad1)") (class "Default")
      (node (ref "JP4") (pin "1") (pinfunction "1_1") (pintype "passive"))
      (node (ref "R1") (pin "1") (pinfunction "1_1") (pintype "passive"))
      (node (ref "R4") (pin "2") (pinfunction "2_2") (pintype "passive"))
    )
    (net (code "73") (name "Net-(R6-Pad1)") (class "Default")
      (node (ref "R6") (pin "1") (pinfunction "1_1") (pintype "passive"))
      (node (ref "SW1") (pin "3") (pinfunction "3_3") (pintype "passive"))
      (node (ref "SW1") (pin "4") (pinfunction "4_4") (pintype "passive"))
    )
    (net (code "74") (name "Net-(R7-Pad1)") (class "Default")
      (node (ref "R7") (pin "1") (pinfunction "1_1") (pintype "passive"))
      (node (ref "SW2") (pin "3") (pinfunction "3_3") (pintype "passive"))
      (node (ref "SW2") (pin "4") (pinfunction "4_4") (pintype "passive"))
    )
    (net (code "75") (name "Net-(U3-VREG_AVDD)") (class "Default")
      (node (ref "C14") (pin "2") (pinfunction "2_2") (pintype "passive"))
      (node (ref "R3") (pin "2") (pinfunction "2_2") (pintype "passive"))
      (node (ref "U3") (pin "61") (pinfunction "VREG_AVDD_61") (pintype "passive"))
    )
    (net (code "76") (name "Net-(U3-VREG_LX)") (class "Default")
      (node (ref "L1") (pin "2") (pinfunction "2_2") (pintype "passive"))
      (node (ref "U3") (pin "63") (pinfunction "VREG_LX_63") (pintype "passive"))
    )
    (net (code "77") (name "Net-(Y1-OUT)") (class "Default")
      (node (ref "C24") (pin "2") (pinfunction "2_2") (pintype "passive"))
      (node (ref "R11") (pin "1") (pinfunction "1_1") (pintype "passive"))
      (node (ref "Y1") (pin "3") (pinfunction "OUT_3") (pintype "passive"))
    )
    (net (code "78") (name "VBUS") (class "Default")
      (node (ref "C21") (pin "2") (pinfunction "2_2") (pintype "passive"))
      (node (ref "C25") (pin "1") (pinfunction "1_1") (pintype "passive"))
      (node (ref "U4") (pin "1") (pinfunction "Vin_1") (pintype "passive"))
      (node (ref "U4") (pin "3") (pinfunction "Shutdown_3") (pintype "passive"))
      (node (ref "U5") (pin "3") (pinfunction "Vin_3") (pintype "passive"))
      (node (ref "X2") (pin "1") (pinfunction "1_1") (pintype "passive"))
      (node (ref "X2") (pin "2") (pinfunction "2_2") (pintype "passive"))
      (node (ref "X2") (pin "3") (pinfunction "3_3") (pintype "passive"))
      (node (ref "X4") (pin "1") (pinfunction "1_1") (pintype "passive"))
      (node (ref "X7") (pin "1") (pinfunction "1_1") (pintype "passive"))
    )
    (net (code "79") (name "unconnected-(X7-Pad4)") (class "Default")
      (node (ref "X7") (pin "4") (pinfunction "4_4") (pintype "passive+no_connect"))
    )
  )
)
